# LocoShield-TMH-ThroughHole.net
KiCad netlist of a schematic drawn in EAGLE
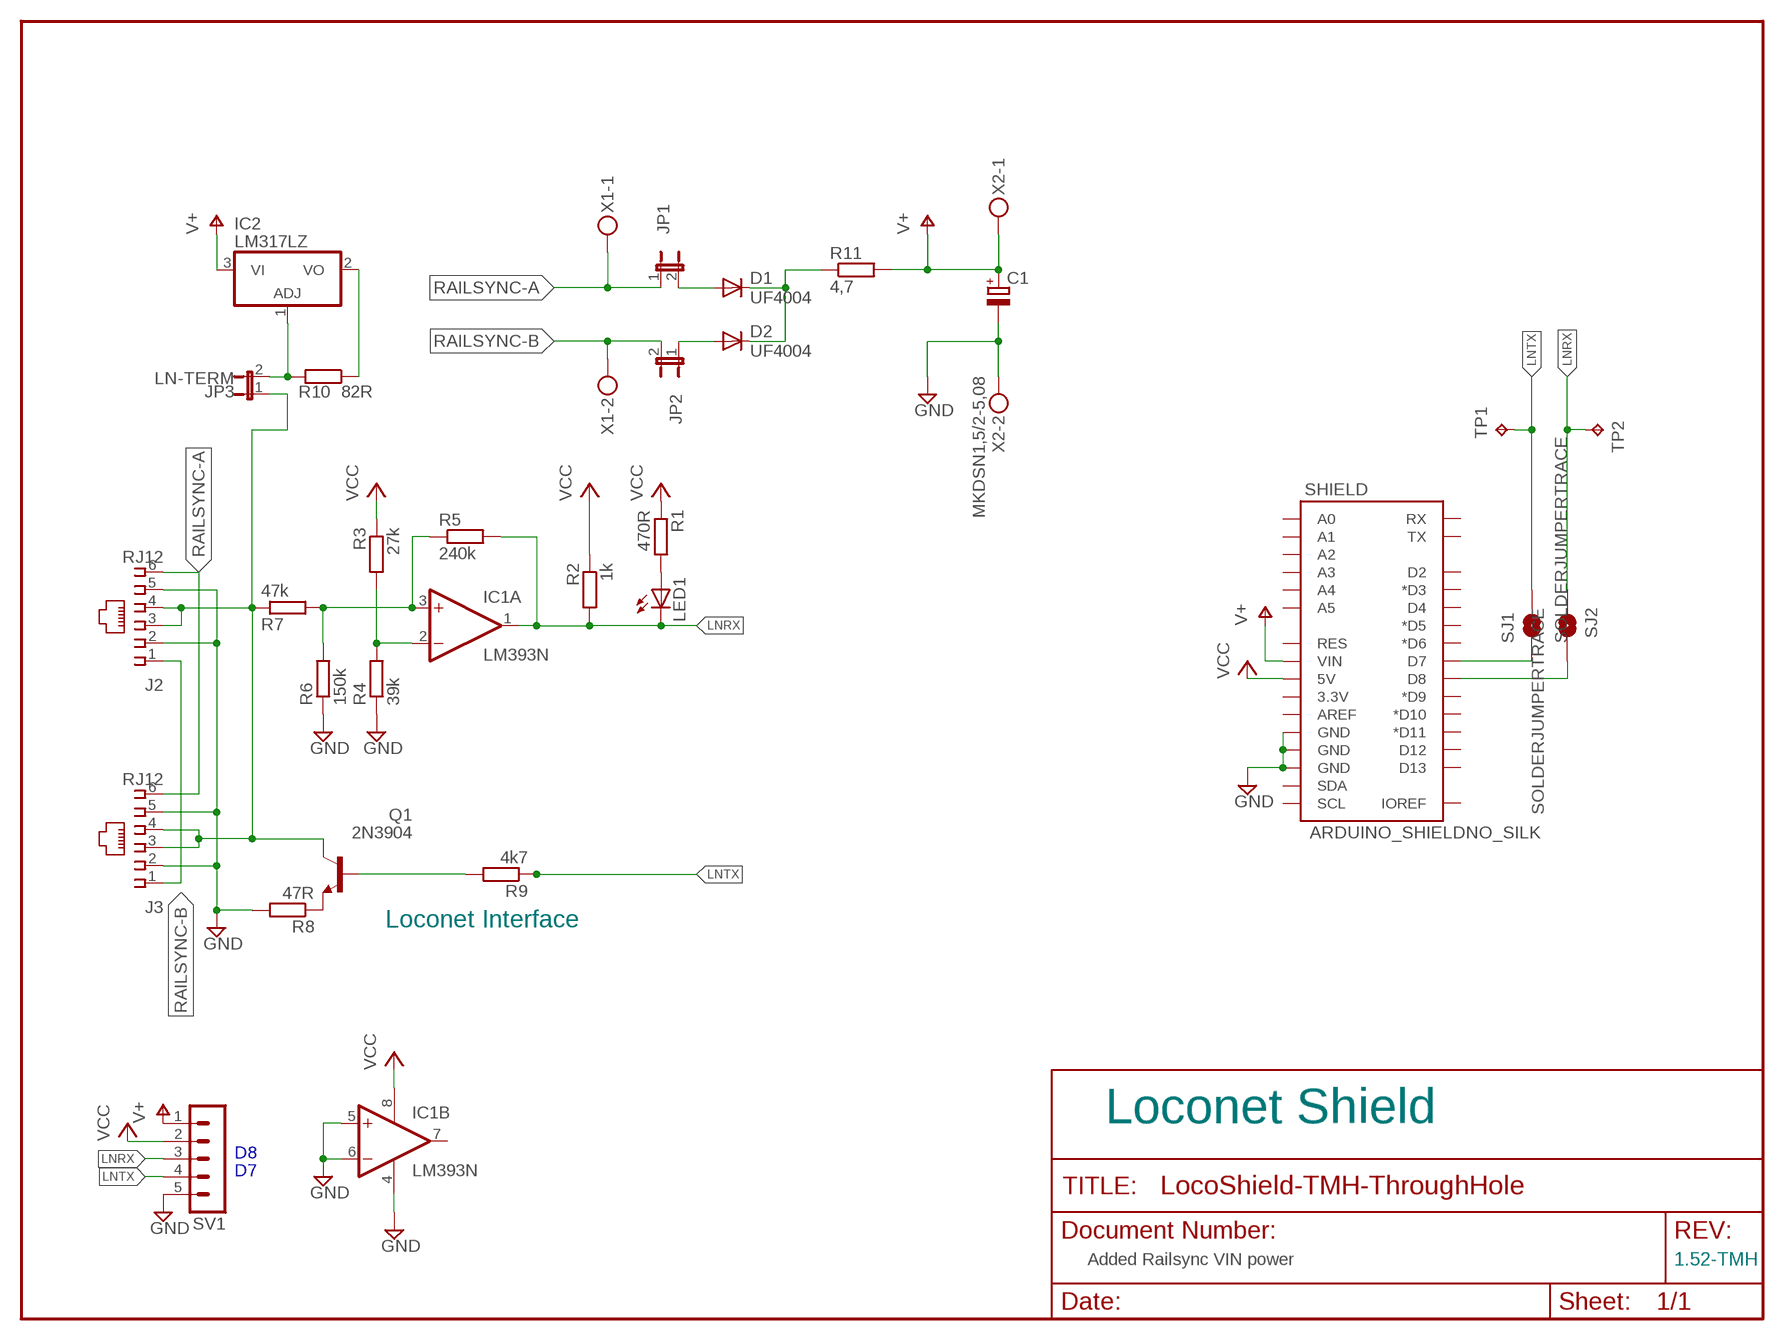
[diagram p0: schematic, sheet 1]

(export (version "E")
  (design (tool "Eeschema 10.0.6"))
  (components
    (comp (ref "C1")
      (value "CPOL-EUE2-5")
      (footprint "eagle-import:E2-5")
      (libsource (lib "eagle-import") (part "CPOL-EUE2-5"))
    )
    (comp (ref "D1")
      (value "UF4004")
      (footprint "eagle-import:DO35-7")
      (libsource (lib "eagle-import") (part "1N4148DO35-7"))
    )
    (comp (ref "D2")
      (value "UF4004")
      (footprint "eagle-import:DO35-7")
      (libsource (lib "eagle-import") (part "1N4148DO35-7"))
    )
    (comp (ref "IC1")
      (value "LM393N")
      (footprint "eagle-import:DIL08")
      (fields (field (name "ELFA") "300-19-446"))
      (libsource (lib "eagle-import") (part "LM393N"))
    )
    (comp (ref "IC2")
      (value "LM317LZ")
      (footprint "eagle-import:TO92")
      (libsource (lib "eagle-import") (part "317LZLM"))
    )
    (comp (ref "J2")
      (value "RJ12")
      (footprint "eagle-import:520250-3")
      (libsource (lib "eagle-import") (part "520250-3"))
    )
    (comp (ref "J3")
      (value "RJ12")
      (footprint "eagle-import:520250-3")
      (libsource (lib "eagle-import") (part "520250-3"))
    )
    (comp (ref "JP1")
      (value "JUMPER-2PTH_LOCK")
      (footprint "eagle-import:1X02_LOCK")
      (libsource (lib "eagle-import") (part "SPCoast_JUMPER-2PTH_LOCK"))
    )
    (comp (ref "JP2")
      (value "JUMPER-2PTH_LOCK")
      (footprint "eagle-import:1X02_LOCK")
      (libsource (lib "eagle-import") (part "SPCoast_JUMPER-2PTH_LOCK"))
    )
    (comp (ref "JP3")
      (value "LN-TERM")
      (footprint "eagle-import:1X02_LOCK")
      (libsource (lib "eagle-import") (part "JUMPER-2PTH_LOCK"))
    )
    (comp (ref "LED1")
      (value "LED3MM")
      (footprint "eagle-import:LED3MM")
      (libsource (lib "eagle-import") (part "LED3MM"))
    )
    (comp (ref "Q1")
      (value "2N3904")
      (footprint "eagle-import:TO92")
      (libsource (lib "eagle-import") (part "2N3904"))
    )
    (comp (ref "R1")
      (value "470R")
      (footprint "eagle-import:0207_10")
      (libsource (lib "eagle-import") (part "R-EU_0207/10"))
    )
    (comp (ref "R2")
      (value "1k")
      (footprint "eagle-import:0207_10")
      (libsource (lib "eagle-import") (part "R-EU_0207/10"))
    )
    (comp (ref "R3")
      (value "27k")
      (footprint "eagle-import:0207_10")
      (libsource (lib "eagle-import") (part "R-EU_0207/10"))
    )
    (comp (ref "R4")
      (value "39k")
      (footprint "eagle-import:0207_10")
      (libsource (lib "eagle-import") (part "R-EU_0207/10"))
    )
    (comp (ref "R5")
      (value "240k")
      (footprint "eagle-import:0207_10")
      (libsource (lib "eagle-import") (part "R-EU_0207/10"))
    )
    (comp (ref "R6")
      (value "150k")
      (footprint "eagle-import:0207_10")
      (libsource (lib "eagle-import") (part "R-EU_0207/10"))
    )
    (comp (ref "R7")
      (value "47k")
      (footprint "eagle-import:0207_10")
      (libsource (lib "eagle-import") (part "R-EU_0207/10"))
    )
    (comp (ref "R8")
      (value "47R")
      (footprint "eagle-import:0207_10")
      (libsource (lib "eagle-import") (part "R-EU_0207/10"))
    )
    (comp (ref "R9")
      (value "4k7")
      (footprint "eagle-import:0207_10")
      (libsource (lib "eagle-import") (part "R-EU_0207/10"))
    )
    (comp (ref "R10")
      (value "82R")
      (footprint "eagle-import:0207_10")
      (libsource (lib "eagle-import") (part "R-EU_0207/10"))
    )
    (comp (ref "R11")
      (value "4,7")
      (footprint "eagle-import:0207_10")
      (libsource (lib "eagle-import") (part "R-EU_0207/10"))
    )
    (comp (ref "SHIELD")
      (value "ARDUINO_SHIELDNO_SILK")
      (footprint "eagle-import:DUEMILANOVE_VIAS")
      (libsource (lib "eagle-import") (part "ARDUINO_SHIELDNO_SILK"))
    )
    (comp (ref "SJ1")
      (value "SOLDERJUMPERTRACE")
      (footprint "eagle-import:SJ_2S-TRACE")
      (libsource (lib "eagle-import") (part "SOLDERJUMPERTRACE"))
    )
    (comp (ref "SJ2")
      (value "SOLDERJUMPERTRACE")
      (footprint "eagle-import:SJ_2S-TRACE")
      (libsource (lib "eagle-import") (part "SOLDERJUMPERTRACE"))
    )
    (comp (ref "SV1")
      (value "MA05-1")
      (footprint "eagle-import:MA05-1")
      (libsource (lib "eagle-import") (part "MA05-1"))
    )
    (comp (ref "TP1")
      (value "TPPAD1-17")
      (footprint "eagle-import:P1-17")
      (libsource (lib "eagle-import") (part "TPPAD1-17"))
    )
    (comp (ref "TP2")
      (value "TPPAD1-17")
      (footprint "eagle-import:P1-17")
      (libsource (lib "eagle-import") (part "TPPAD1-17"))
    )
    (comp (ref "X1")
      (value "MKDSN1,5/2-5,08")
      (footprint "eagle-import:MKDSN1,5_2-5,08")
      (fields (field (name "ELFA") "148-45-038"))
      (libsource (lib "eagle-import") (part "MKDSN1,5/2-5,08"))
    )
    (comp (ref "X2")
      (value "MKDSN1,5/2-5,08")
      (footprint "eagle-import:MKDSN1,5_2-5,08")
      (fields (field (name "ELFA") "148-45-038"))
      (libsource (lib "eagle-import") (part "MKDSN1,5/2-5,08"))
    )
  )
  (nets
    (net (code "1") (name "GND") (class "Default")
      (node (ref "C1") (pin "-") (pinfunction "-_-") (pintype "passive"))
      (node (ref "IC1") (pin "4") (pinfunction "V-_4") (pintype "power_in"))
      (node (ref "IC1") (pin "5") (pinfunction "+IN_5") (pintype "input"))
      (node (ref "IC1") (pin "6") (pinfunction "-IN_6") (pintype "input"))
      (node (ref "J2") (pin "2") (pinfunction "2_2") (pintype "passive"))
      (node (ref "J2") (pin "5") (pinfunction "5_5") (pintype "passive"))
      (node (ref "J3") (pin "2") (pinfunction "2_2") (pintype "passive"))
      (node (ref "J3") (pin "5") (pinfunction "5_5") (pintype "passive"))
      (node (ref "R4") (pin "1") (pinfunction "1_1") (pintype "passive"))
      (node (ref "R6") (pin "1") (pinfunction "1_1") (pintype "passive"))
      (node (ref "R8") (pin "2") (pinfunction "2_2") (pintype "passive"))
      (node (ref "SHIELD") (pin "GND@0") (pinfunction "GND_GND@0") (pintype "bidirectional"))
      (node (ref "SHIELD") (pin "GND@1") (pinfunction "GND_GND@1") (pintype "bidirectional"))
      (node (ref "SHIELD") (pin "GND@2") (pinfunction "GND_GND@2") (pintype "bidirectional"))
      (node (ref "SV1") (pin "5") (pinfunction "5_5") (pintype "passive"))
      (node (ref "X2") (pin "2") (pinfunction "KL_2") (pintype "passive"))
    )
    (net (code "2") (name "LNRX") (class "Default")
      (node (ref "IC1") (pin "1") (pinfunction "OUT_1") (pintype "output"))
      (node (ref "LED1") (pin "K") (pinfunction "C_K") (pintype "passive"))
      (node (ref "R2") (pin "2") (pinfunction "2_2") (pintype "passive"))
      (node (ref "R5") (pin "2") (pinfunction "2_2") (pintype "passive"))
      (node (ref "SJ2") (pin "1") (pinfunction "1_1") (pintype "passive"))
      (node (ref "SV1") (pin "3") (pinfunction "3_3") (pintype "passive"))
      (node (ref "TP2") (pin "TP") (pinfunction "TP_TP") (pintype "input"))
    )
    (net (code "3") (name "LNTX") (class "Default")
      (node (ref "R9") (pin "1") (pinfunction "1_1") (pintype "passive"))
      (node (ref "SJ1") (pin "2") (pinfunction "2_2") (pintype "passive"))
      (node (ref "SV1") (pin "4") (pinfunction "4_4") (pintype "passive"))
      (node (ref "TP1") (pin "TP") (pinfunction "TP_TP") (pintype "input"))
    )
    (net (code "4") (name "Net-(D1-PadA)") (class "Default")
      (node (ref "D1") (pin "A") (pinfunction "A_A") (pintype "passive"))
      (node (ref "JP1") (pin "2") (pinfunction "2_2") (pintype "passive"))
    )
    (net (code "5") (name "Net-(D1-PadC)") (class "Default")
      (node (ref "D1") (pin "C") (pinfunction "C_C") (pintype "passive"))
      (node (ref "D2") (pin "C") (pinfunction "C_C") (pintype "passive"))
      (node (ref "R11") (pin "1") (pinfunction "1_1") (pintype "passive"))
    )
    (net (code "6") (name "Net-(D2-PadA)") (class "Default")
      (node (ref "D2") (pin "A") (pinfunction "A_A") (pintype "passive"))
      (node (ref "JP2") (pin "1") (pinfunction "1_1") (pintype "passive"))
    )
    (net (code "7") (name "Net-(IC1A-+IN)") (class "Default")
      (node (ref "IC1") (pin "3") (pinfunction "+IN_3") (pintype "input"))
      (node (ref "R5") (pin "1") (pinfunction "1_1") (pintype "passive"))
      (node (ref "R6") (pin "2") (pinfunction "2_2") (pintype "passive"))
      (node (ref "R7") (pin "2") (pinfunction "2_2") (pintype "passive"))
    )
    (net (code "8") (name "Net-(IC1A--IN)") (class "Default")
      (node (ref "IC1") (pin "2") (pinfunction "-IN_2") (pintype "input"))
      (node (ref "R3") (pin "2") (pinfunction "2_2") (pintype "passive"))
      (node (ref "R4") (pin "2") (pinfunction "2_2") (pintype "passive"))
    )
    (net (code "9") (name "Net-(IC2-ADJ)") (class "Default")
      (node (ref "IC2") (pin "1") (pinfunction "ADJ_1") (pintype "input"))
      (node (ref "JP3") (pin "2") (pinfunction "2_2") (pintype "passive"))
      (node (ref "R10") (pin "2") (pinfunction "2_2") (pintype "passive"))
    )
    (net (code "10") (name "Net-(IC2-VO)") (class "Default")
      (node (ref "IC2") (pin "2") (pinfunction "VO_2") (pintype "passive"))
      (node (ref "R10") (pin "1") (pinfunction "1_1") (pintype "passive"))
    )
    (net (code "11") (name "Net-(LED1-PadA)") (class "Default")
      (node (ref "LED1") (pin "A") (pinfunction "A_A") (pintype "passive"))
      (node (ref "R1") (pin "2") (pinfunction "2_2") (pintype "passive"))
    )
    (net (code "12") (name "Net-(Q1-B)") (class "Default")
      (node (ref "Q1") (pin "2") (pinfunction "B_2") (pintype "passive"))
      (node (ref "R9") (pin "2") (pinfunction "2_2") (pintype "passive"))
    )
    (net (code "13") (name "Net-(Q1-C)") (class "Default")
      (node (ref "J2") (pin "3") (pinfunction "3_3") (pintype "passive"))
      (node (ref "J2") (pin "4") (pinfunction "4_4") (pintype "passive"))
      (node (ref "J3") (pin "3") (pinfunction "3_3") (pintype "passive"))
      (node (ref "J3") (pin "4") (pinfunction "4_4") (pintype "passive"))
      (node (ref "JP3") (pin "1") (pinfunction "1_1") (pintype "passive"))
      (node (ref "Q1") (pin "1") (pinfunction "C_1") (pintype "passive"))
      (node (ref "R7") (pin "1") (pinfunction "1_1") (pintype "passive"))
    )
    (net (code "14") (name "Net-(Q1-E)") (class "Default")
      (node (ref "Q1") (pin "3") (pinfunction "E_3") (pintype "passive"))
      (node (ref "R8") (pin "1") (pinfunction "1_1") (pintype "passive"))
    )
    (net (code "15") (name "Net-(SHIELD-PadD7)") (class "Default")
      (node (ref "SHIELD") (pin "D7") (pinfunction "D7_D7") (pintype "bidirectional"))
      (node (ref "SJ1") (pin "1") (pinfunction "1_1") (pintype "passive"))
    )
    (net (code "16") (name "Net-(SHIELD-PadD8)") (class "Default")
      (node (ref "SHIELD") (pin "D8") (pinfunction "D8_D8") (pintype "bidirectional"))
      (node (ref "SJ2") (pin "2") (pinfunction "2_2") (pintype "passive"))
    )
    (net (code "17") (name "RAILSYNC-A") (class "Default")
      (node (ref "J2") (pin "6") (pinfunction "6_6") (pintype "passive"))
      (node (ref "J3") (pin "6") (pinfunction "6_6") (pintype "passive"))
      (node (ref "JP1") (pin "1") (pinfunction "1_1") (pintype "passive"))
      (node (ref "X1") (pin "1") (pinfunction "KL_1") (pintype "passive"))
    )
    (net (code "18") (name "RAILSYNC-B") (class "Default")
      (node (ref "J2") (pin "1") (pinfunction "1_1") (pintype "passive"))
      (node (ref "J3") (pin "1") (pinfunction "1_1") (pintype "passive"))
      (node (ref "JP2") (pin "2") (pinfunction "2_2") (pintype "passive"))
      (node (ref "X1") (pin "2") (pinfunction "KL_2") (pintype "passive"))
    )
    (net (code "19") (name "V+") (class "Default")
      (node (ref "C1") (pin "+") (pinfunction "+_+") (pintype "passive"))
      (node (ref "IC2") (pin "3") (pinfunction "VI_3") (pintype "input"))
      (node (ref "R11") (pin "2") (pinfunction "2_2") (pintype "passive"))
      (node (ref "SHIELD") (pin "VIN") (pinfunction "VIN_VIN") (pintype "bidirectional"))
      (node (ref "SV1") (pin "1") (pinfunction "1_1") (pintype "passive"))
      (node (ref "X2") (pin "1") (pinfunction "KL_1") (pintype "passive"))
    )
    (net (code "20") (name "VCC") (class "Default")
      (node (ref "IC1") (pin "8") (pinfunction "V+_8") (pintype "power_in"))
      (node (ref "R1") (pin "1") (pinfunction "1_1") (pintype "passive"))
      (node (ref "R2") (pin "1") (pinfunction "1_1") (pintype "passive"))
      (node (ref "R3") (pin "1") (pinfunction "1_1") (pintype "passive"))
      (node (ref "SHIELD") (pin "5V") (pinfunction "5V_5V") (pintype "bidirectional"))
      (node (ref "SV1") (pin "2") (pinfunction "2_2") (pintype "passive"))
    )
    (net (code "21") (name "unconnected-(IC1B-OUT-Pad7)") (class "Default")
      (node (ref "IC1") (pin "7") (pinfunction "OUT_7") (pintype "output"))
    )
    (net (code "22") (name "unconnected-(SHIELD-*D3-PadD3)") (class "Default")
      (node (ref "SHIELD") (pin "D3") (pinfunction "*D3_D3") (pintype "bidirectional"))
    )
    (net (code "23") (name "unconnected-(SHIELD-*D5-PadD5)") (class "Default")
      (node (ref "SHIELD") (pin "D5") (pinfunction "*D5_D5") (pintype "bidirectional"))
    )
    (net (code "24") (name "unconnected-(SHIELD-*D6-PadD6)") (class "Default")
      (node (ref "SHIELD") (pin "D6") (pinfunction "*D6_D6") (pintype "bidirectional"))
    )
    (net (code "25") (name "unconnected-(SHIELD-*D9-PadD9)") (class "Default")
      (node (ref "SHIELD") (pin "D9") (pinfunction "*D9_D9") (pintype "bidirectional"))
    )
    (net (code "26") (name "unconnected-(SHIELD-*D10-PadD10)") (class "Default")
      (node (ref "SHIELD") (pin "D10") (pinfunction "*D10_D10") (pintype "bidirectional"))
    )
    (net (code "27") (name "unconnected-(SHIELD-*D11-PadD11)") (class "Default")
      (node (ref "SHIELD") (pin "D11") (pinfunction "*D11_D11") (pintype "bidirectional"))
    )
    (net (code "28") (name "unconnected-(SHIELD-Pad3.3V)") (class "Default")
      (node (ref "SHIELD") (pin "3.3V") (pinfunction "3.3V_3.3V") (pintype "bidirectional"))
    )
    (net (code "29") (name "unconnected-(SHIELD-PadA0)") (class "Default")
      (node (ref "SHIELD") (pin "A0") (pinfunction "A0_A0") (pintype "bidirectional"))
    )
    (net (code "30") (name "unconnected-(SHIELD-PadA1)") (class "Default")
      (node (ref "SHIELD") (pin "A1") (pinfunction "A1_A1") (pintype "bidirectional"))
    )
    (net (code "31") (name "unconnected-(SHIELD-PadA2)") (class "Default")
      (node (ref "SHIELD") (pin "A2") (pinfunction "A2_A2") (pintype "bidirectional"))
    )
    (net (code "32") (name "unconnected-(SHIELD-PadA3)") (class "Default")
      (node (ref "SHIELD") (pin "A3") (pinfunction "A3_A3") (pintype "bidirectional"))
    )
    (net (code "33") (name "unconnected-(SHIELD-PadA4)") (class "Default")
      (node (ref "SHIELD") (pin "A4") (pinfunction "A4_A4") (pintype "bidirectional"))
    )
    (net (code "34") (name "unconnected-(SHIELD-PadA5)") (class "Default")
      (node (ref "SHIELD") (pin "A5") (pinfunction "A5_A5") (pintype "bidirectional"))
    )
    (net (code "35") (name "unconnected-(SHIELD-PadAREF)") (class "Default")
      (node (ref "SHIELD") (pin "AREF") (pinfunction "AREF_AREF") (pintype "bidirectional"))
    )
    (net (code "36") (name "unconnected-(SHIELD-PadD2)") (class "Default")
      (node (ref "SHIELD") (pin "D2") (pinfunction "D2_D2") (pintype "bidirectional"))
    )
    (net (code "37") (name "unconnected-(SHIELD-PadD4)") (class "Default")
      (node (ref "SHIELD") (pin "D4") (pinfunction "D4_D4") (pintype "bidirectional"))
    )
    (net (code "38") (name "unconnected-(SHIELD-PadD12)") (class "Default")
      (node (ref "SHIELD") (pin "D12") (pinfunction "D12_D12") (pintype "bidirectional"))
    )
    (net (code "39") (name "unconnected-(SHIELD-PadD13)") (class "Default")
      (node (ref "SHIELD") (pin "D13") (pinfunction "D13_D13") (pintype "bidirectional"))
    )
    (net (code "40") (name "unconnected-(SHIELD-PadIOREF)") (class "Default")
      (node (ref "SHIELD") (pin "IOREF") (pinfunction "IOREF_IOREF") (pintype "bidirectional"))
    )
    (net (code "41") (name "unconnected-(SHIELD-PadRES)") (class "Default")
      (node (ref "SHIELD") (pin "RES") (pinfunction "RES_RES") (pintype "bidirectional"))
    )
    (net (code "42") (name "unconnected-(SHIELD-PadRX)") (class "Default")
      (node (ref "SHIELD") (pin "RX") (pinfunction "RX_RX") (pintype "bidirectional"))
    )
    (net (code "43") (name "unconnected-(SHIELD-PadSCL)") (class "Default")
      (node (ref "SHIELD") (pin "SCL") (pinfunction "SCL_SCL") (pintype "bidirectional"))
    )
    (net (code "44") (name "unconnected-(SHIELD-PadSDA)") (class "Default")
      (node (ref "SHIELD") (pin "SDA") (pinfunction "SDA_SDA") (pintype "bidirectional"))
    )
    (net (code "45") (name "unconnected-(SHIELD-PadTX)") (class "Default")
      (node (ref "SHIELD") (pin "TX") (pinfunction "TX_TX") (pintype "bidirectional"))
    )
  )
)
